# bp.net
KiCad netlist of a schematic drawn in EAGLE
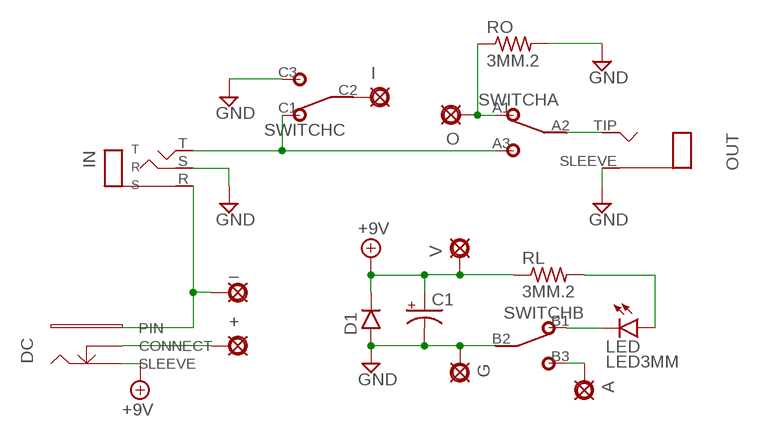
[diagram p0: schematic, sheet 1]

(export (version "E")
  (design (tool "Eeschema 10.0.6"))
  (components
    (comp (ref "+")
      (value "PAD")
      (footprint "eagle-import:SQUARE")
      (libsource (lib "eagle-import") (part "PAD"))
    )
    (comp (ref "A")
      (value "PAD8")
      (footprint "eagle-import:OCTOGON")
      (libsource (lib "eagle-import") (part "PAD8"))
    )
    (comp (ref "C1")
      (value "0631")
      (footprint "eagle-import:063_025")
      (libsource (lib "eagle-import") (part "0631"))
    )
    (comp (ref "D1")
      (value "1N400X.3")
      (footprint "eagle-import:DO41-3")
      (libsource (lib "eagle-import") (part "1N400X.3"))
    )
    (comp (ref "DC")
      (value "DCP2")
      (footprint "eagle-import:DC_PADS2")
      (libsource (lib "eagle-import") (part "DCP2"))
    )
    (comp (ref "G")
      (value "PADO")
      (footprint "eagle-import:ROUND")
      (libsource (lib "eagle-import") (part "PADO"))
    )
    (comp (ref "I")
      (value "PADO")
      (footprint "eagle-import:ROUND")
      (libsource (lib "eagle-import") (part "PADO"))
    )
    (comp (ref "IN")
      (value "STEREOP")
      (footprint "eagle-import:STEREO_PADS")
      (libsource (lib "eagle-import") (part "STEREOP"))
    )
    (comp (ref "LED")
      (value "LED3MM")
      (footprint "eagle-import:LED3MM")
      (libsource (lib "eagle-import") (part "LED3MM"))
    )
    (comp (ref "O")
      (value "PADO")
      (footprint "eagle-import:ROUND")
      (libsource (lib "eagle-import") (part "PADO"))
    )
    (comp (ref "OUT")
      (value "MONOP")
      (footprint "eagle-import:TWO_PADS")
      (libsource (lib "eagle-import") (part "MONOP"))
    )
    (comp (ref "RL")
      (value "3MM.2")
      (footprint "eagle-import:R0204_2")
      (libsource (lib "eagle-import") (part "3MM.2"))
    )
    (comp (ref "RO")
      (value "3MM.2")
      (footprint "eagle-import:R0204_2")
      (libsource (lib "eagle-import") (part "3MM.2"))
    )
    (comp (ref "SWITCH")
      (value "3PDTBLUE")
      (footprint "eagle-import:CHINABLUE")
      (libsource (lib "eagle-import") (part "3PDTBLUE"))
    )
    (comp (ref "V")
      (value "PADO")
      (footprint "eagle-import:ROUND")
      (libsource (lib "eagle-import") (part "PADO"))
    )
    (comp (ref "_")
      (value "PADO")
      (footprint "eagle-import:ROUND")
      (libsource (lib "eagle-import") (part "PADO"))
    )
  )
  (nets
    (net (code "1") (name "+9V") (class "Default")
      (node (ref "C1") (pin "+") (pinfunction "+_+") (pintype "passive"))
      (node (ref "D1") (pin "C") (pinfunction "C_C") (pintype "passive"))
      (node (ref "DC") (pin "S") (pinfunction "SLEEVE_S") (pintype "passive"))
      (node (ref "RL") (pin "1") (pinfunction "1_1") (pintype "passive"))
      (node (ref "V") (pin "1") (pinfunction "PAD_1") (pintype "passive"))
    )
    (net (code "2") (name "GND") (class "Default")
      (node (ref "C1") (pin "-") (pinfunction "-_-") (pintype "passive"))
      (node (ref "D1") (pin "A") (pinfunction "A_A") (pintype "passive"))
      (node (ref "G") (pin "1") (pinfunction "PAD_1") (pintype "passive"))
      (node (ref "IN") (pin "S") (pinfunction "R_S") (pintype "passive"))
      (node (ref "OUT") (pin "SLEEVE") (pinfunction "SLEEVE_SLEEVE") (pintype "passive"))
      (node (ref "RO") (pin "2") (pinfunction "2_2") (pintype "passive"))
      (node (ref "SWITCH") (pin "B2") (pinfunction "2_B2") (pintype "passive"))
      (node (ref "SWITCH") (pin "C3") (pinfunction "3_C3") (pintype "passive"))
    )
    (net (code "3") (name "Net-(+-PAD)") (class "Default")
      (node (ref "+") (pin "1") (pinfunction "PAD_1") (pintype "passive"))
      (node (ref "DC") (pin "C") (pinfunction "CONNECT_C") (pintype "passive"))
    )
    (net (code "4") (name "Net-(A-PAD)") (class "Default")
      (node (ref "A") (pin "1") (pinfunction "PAD_1") (pintype "passive"))
      (node (ref "SWITCH") (pin "B3") (pinfunction "3_B3") (pintype "passive"))
    )
    (net (code "5") (name "Net-(DC-PIN)") (class "Default")
      (node (ref "DC") (pin "P") (pinfunction "PIN_P") (pintype "passive"))
      (node (ref "IN") (pin "R") (pinfunction "S_R") (pintype "passive"))
      (node (ref "_") (pin "1") (pinfunction "PAD_1") (pintype "passive"))
    )
    (net (code "6") (name "Net-(I-PAD)") (class "Default")
      (node (ref "I") (pin "1") (pinfunction "PAD_1") (pintype "passive"))
      (node (ref "SWITCH") (pin "C2") (pinfunction "2_C2") (pintype "passive"))
    )
    (net (code "7") (name "Net-(LED-C)") (class "Default")
      (node (ref "LED") (pin "K") (pinfunction "C_K") (pintype "passive"))
      (node (ref "SWITCH") (pin "B1") (pinfunction "1_B1") (pintype "passive"))
    )
    (net (code "8") (name "Net-(LED-PadA)") (class "Default")
      (node (ref "LED") (pin "A") (pinfunction "A_A") (pintype "passive"))
      (node (ref "RL") (pin "2") (pinfunction "2_2") (pintype "passive"))
    )
    (net (code "9") (name "Net-(O-PAD)") (class "Default")
      (node (ref "O") (pin "1") (pinfunction "PAD_1") (pintype "passive"))
      (node (ref "RO") (pin "1") (pinfunction "1_1") (pintype "passive"))
      (node (ref "SWITCH") (pin "A1") (pinfunction "1_A1") (pintype "passive"))
    )
    (net (code "10") (name "Net-(SWITCHA-2)") (class "Default")
      (node (ref "OUT") (pin "TIP") (pinfunction "TIP_TIP") (pintype "passive"))
      (node (ref "SWITCH") (pin "A2") (pinfunction "2_A2") (pintype "passive"))
    )
    (net (code "11") (name "Net-(SWITCHA-3)") (class "Default")
      (node (ref "IN") (pin "T") (pinfunction "T_T") (pintype "passive"))
      (node (ref "SWITCH") (pin "A3") (pinfunction "3_A3") (pintype "passive"))
      (node (ref "SWITCH") (pin "C1") (pinfunction "1_C1") (pintype "passive"))
    )
  )
)
